# lvpsu.net
KiCad netlist of a schematic drawn in EAGLE
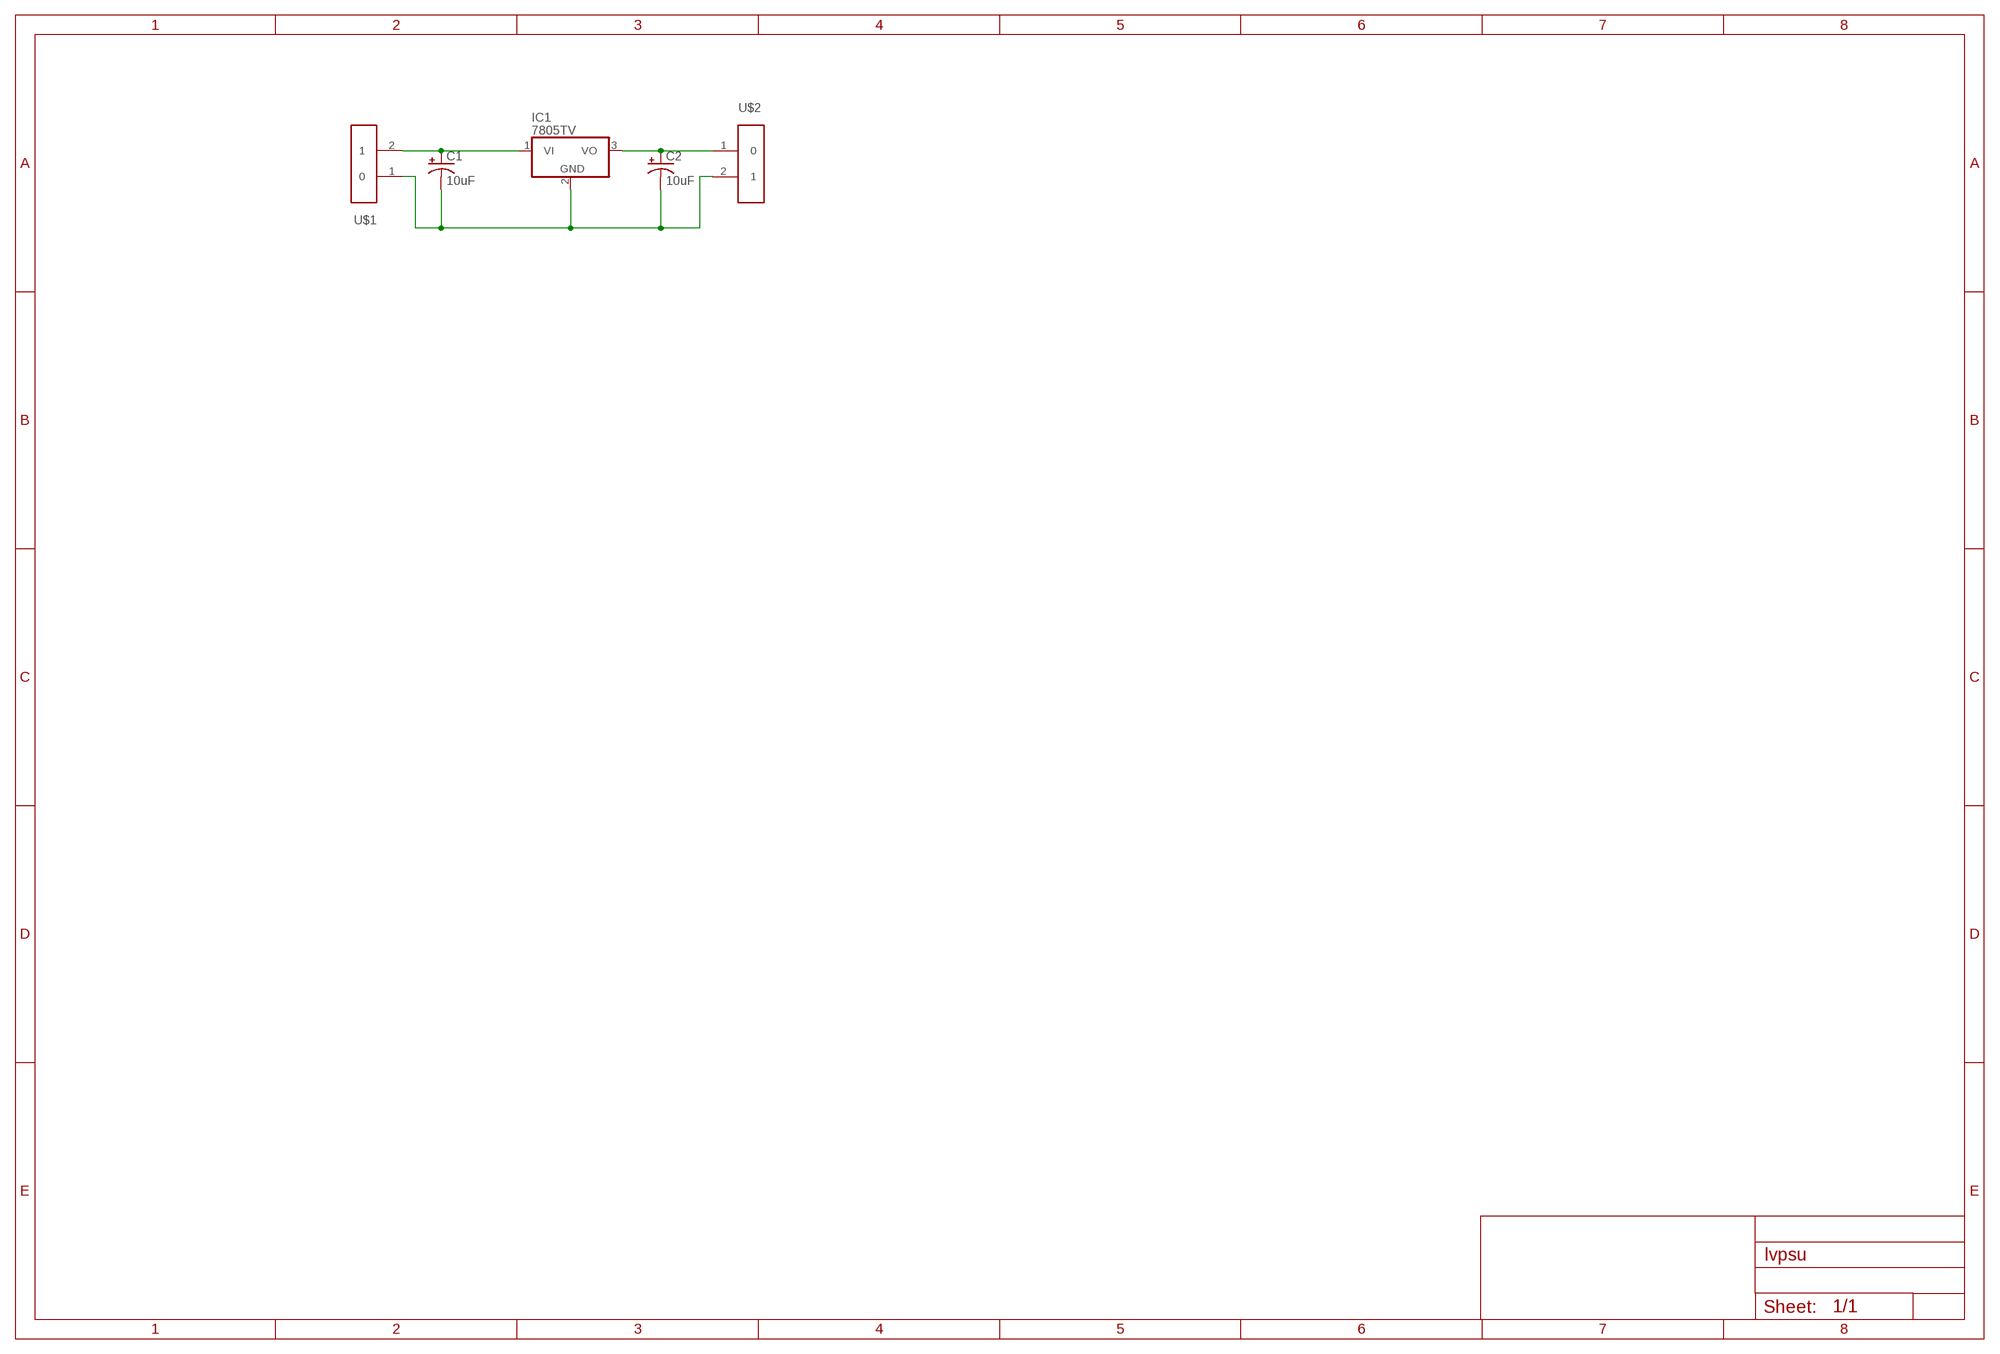
[diagram p0: schematic, sheet 1]

(export (version "E")
  (design (tool "Eeschema 10.0.6"))
  (components
    (comp (ref "C1")
      (value "10uF")
      (footprint "eagle-import:E2,5-5")
      (libsource (lib "eagle-import") (part "CPOL-USE2.5-5"))
    )
    (comp (ref "C2")
      (value "10uF")
      (footprint "eagle-import:E2,5-5")
      (libsource (lib "eagle-import") (part "CPOL-USE2.5-5"))
    )
    (comp (ref "IC1")
      (value "7805TV")
      (footprint "eagle-import:TO220V")
      (libsource (lib "eagle-import") (part "78TV05"))
    )
    (comp (ref "U$1")
      (value "ED2609")
      (footprint "eagle-import:ED2609")
      (libsource (lib "eagle-import") (part "ED2609"))
    )
    (comp (ref "U$2")
      (value "ED2609")
      (footprint "eagle-import:ED2609")
      (libsource (lib "eagle-import") (part "ED2609"))
    )
  )
  (nets
    (net (code "1") (name "Net-(IC1-GND)") (class "Default")
      (node (ref "C1") (pin "-") (pinfunction "-_-") (pintype "passive"))
      (node (ref "C2") (pin "-") (pinfunction "-_-") (pintype "passive"))
      (node (ref "IC1") (pin "2") (pinfunction "GND_2") (pintype "passive"))
      (node (ref "U$1") (pin "1") (pinfunction "0_1") (pintype "bidirectional"))
      (node (ref "U$2") (pin "2") (pinfunction "1_2") (pintype "bidirectional"))
    )
    (net (code "2") (name "Net-(IC1-VI)") (class "Default")
      (node (ref "C1") (pin "+") (pinfunction "+_+") (pintype "passive"))
      (node (ref "IC1") (pin "1") (pinfunction "VI_1") (pintype "input"))
      (node (ref "U$1") (pin "2") (pinfunction "1_2") (pintype "bidirectional"))
    )
    (net (code "3") (name "Net-(IC1-VO)") (class "Default")
      (node (ref "C2") (pin "+") (pinfunction "+_+") (pintype "passive"))
      (node (ref "IC1") (pin "3") (pinfunction "VO_3") (pintype "passive"))
      (node (ref "U$2") (pin "1") (pinfunction "0_1") (pintype "bidirectional"))
    )
  )
)
